# Sheet2.net
KiCad netlist of a schematic drawn in Altium Designer
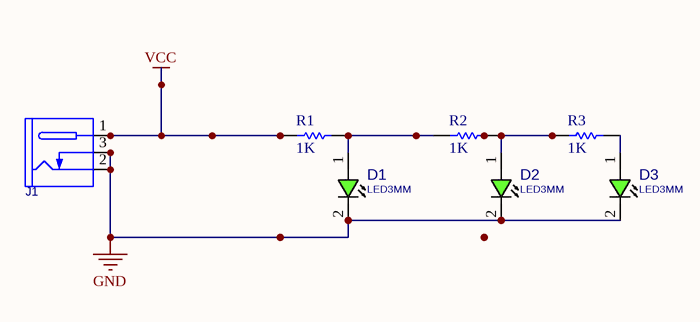
[diagram p0: Sheet2.SchDoc]

(export (version "E")
  (design (tool "Eeschema 10.0.6"))
  (components
    (comp (ref "D1")
      (value "LED3MM")
      (footprint "LED3MM")
      (description "LED, THD, 3MM, GREEN")
      (fields (field (name "MANF") "MANF") (field (name "MANF_P#") "MANF_PART#"))
      (libsource (lib "led(diode)") (part "LED_THD_3MM"))
    )
    (comp (ref "D2")
      (value "LED3MM")
      (footprint "LED3MM")
      (description "LED, THD, 3MM, GREEN")
      (fields (field (name "MANF") "MANF") (field (name "MANF_P#") "MANF_PART#"))
      (libsource (lib "led(diode)") (part "LED_THD_3MM"))
    )
    (comp (ref "D3")
      (value "LED3MM")
      (footprint "LED3MM")
      (description "LED, THD, 3MM, GREEN")
      (fields (field (name "MANF") "MANF") (field (name "MANF_P#") "MANF_PART#"))
      (libsource (lib "led(diode)") (part "LED_THD_3MM"))
    )
    (comp (ref "J1")
      (value "DC_POWER_JACK")
      (footprint "JAC_PWR1")
      (description "CONN, PWR JACK DC, PLUG DIAM 1.0MM RA THD")
      (fields (field (name "MANF") "CUI STACK") (field (name "MANF_P#") "PJ-031CH, PJ-031C"))
      (libsource (lib "conn_powerJack") (part "CONN_PWR_JACKR1"))
    )
    (comp (ref "R1")
      (value "1K")
      (description "Resistor")
      (libsource (lib "Simulation Generic Components") (part "Resistor"))
    )
    (comp (ref "R2")
      (value "1K")
      (description "Resistor")
      (libsource (lib "Simulation Generic Components") (part "Resistor"))
    )
    (comp (ref "R3")
      (value "1K")
      (description "Resistor")
      (libsource (lib "Simulation Generic Components") (part "Resistor"))
    )
  )
  (nets
    (net (code "1") (name "GND") (class "Default")
      (node (ref "D1") (pin "2") (pinfunction "CATHODE_2") (pintype "passive"))
      (node (ref "D2") (pin "2") (pinfunction "CATHODE_2") (pintype "passive"))
      (node (ref "D3") (pin "2") (pinfunction "CATHODE_2") (pintype "passive"))
      (node (ref "J1") (pin "2") (pinfunction "SLEEVE_2") (pintype "power_in"))
      (node (ref "J1") (pin "3") (pinfunction "INSERTION_DET_3") (pintype "power_in"))
    )
    (net (code "2") (name "Net-(D1-ANODE)") (class "Default")
      (node (ref "D1") (pin "1") (pinfunction "ANODE_1") (pintype "passive"))
      (node (ref "R1") (pin "2") (pinfunction "2_2") (pintype "passive"))
      (node (ref "R2") (pin "1") (pinfunction "1_1") (pintype "passive"))
    )
    (net (code "3") (name "Net-(D2-ANODE)") (class "Default")
      (node (ref "D2") (pin "1") (pinfunction "ANODE_1") (pintype "passive"))
      (node (ref "R2") (pin "2") (pinfunction "2_2") (pintype "passive"))
      (node (ref "R3") (pin "1") (pinfunction "1_1") (pintype "passive"))
    )
    (net (code "4") (name "Net-(D3-ANODE)") (class "Default")
      (node (ref "D3") (pin "1") (pinfunction "ANODE_1") (pintype "passive"))
      (node (ref "R3") (pin "2") (pinfunction "2_2") (pintype "passive"))
    )
    (net (code "5") (name "VCC") (class "Default")
      (node (ref "J1") (pin "1") (pinfunction "TIP_1") (pintype "power_in"))
      (node (ref "R1") (pin "1") (pinfunction "1_1") (pintype "passive"))
    )
  )
)
